# RingBottom.net
KiCad netlist of a schematic drawn in EAGLE
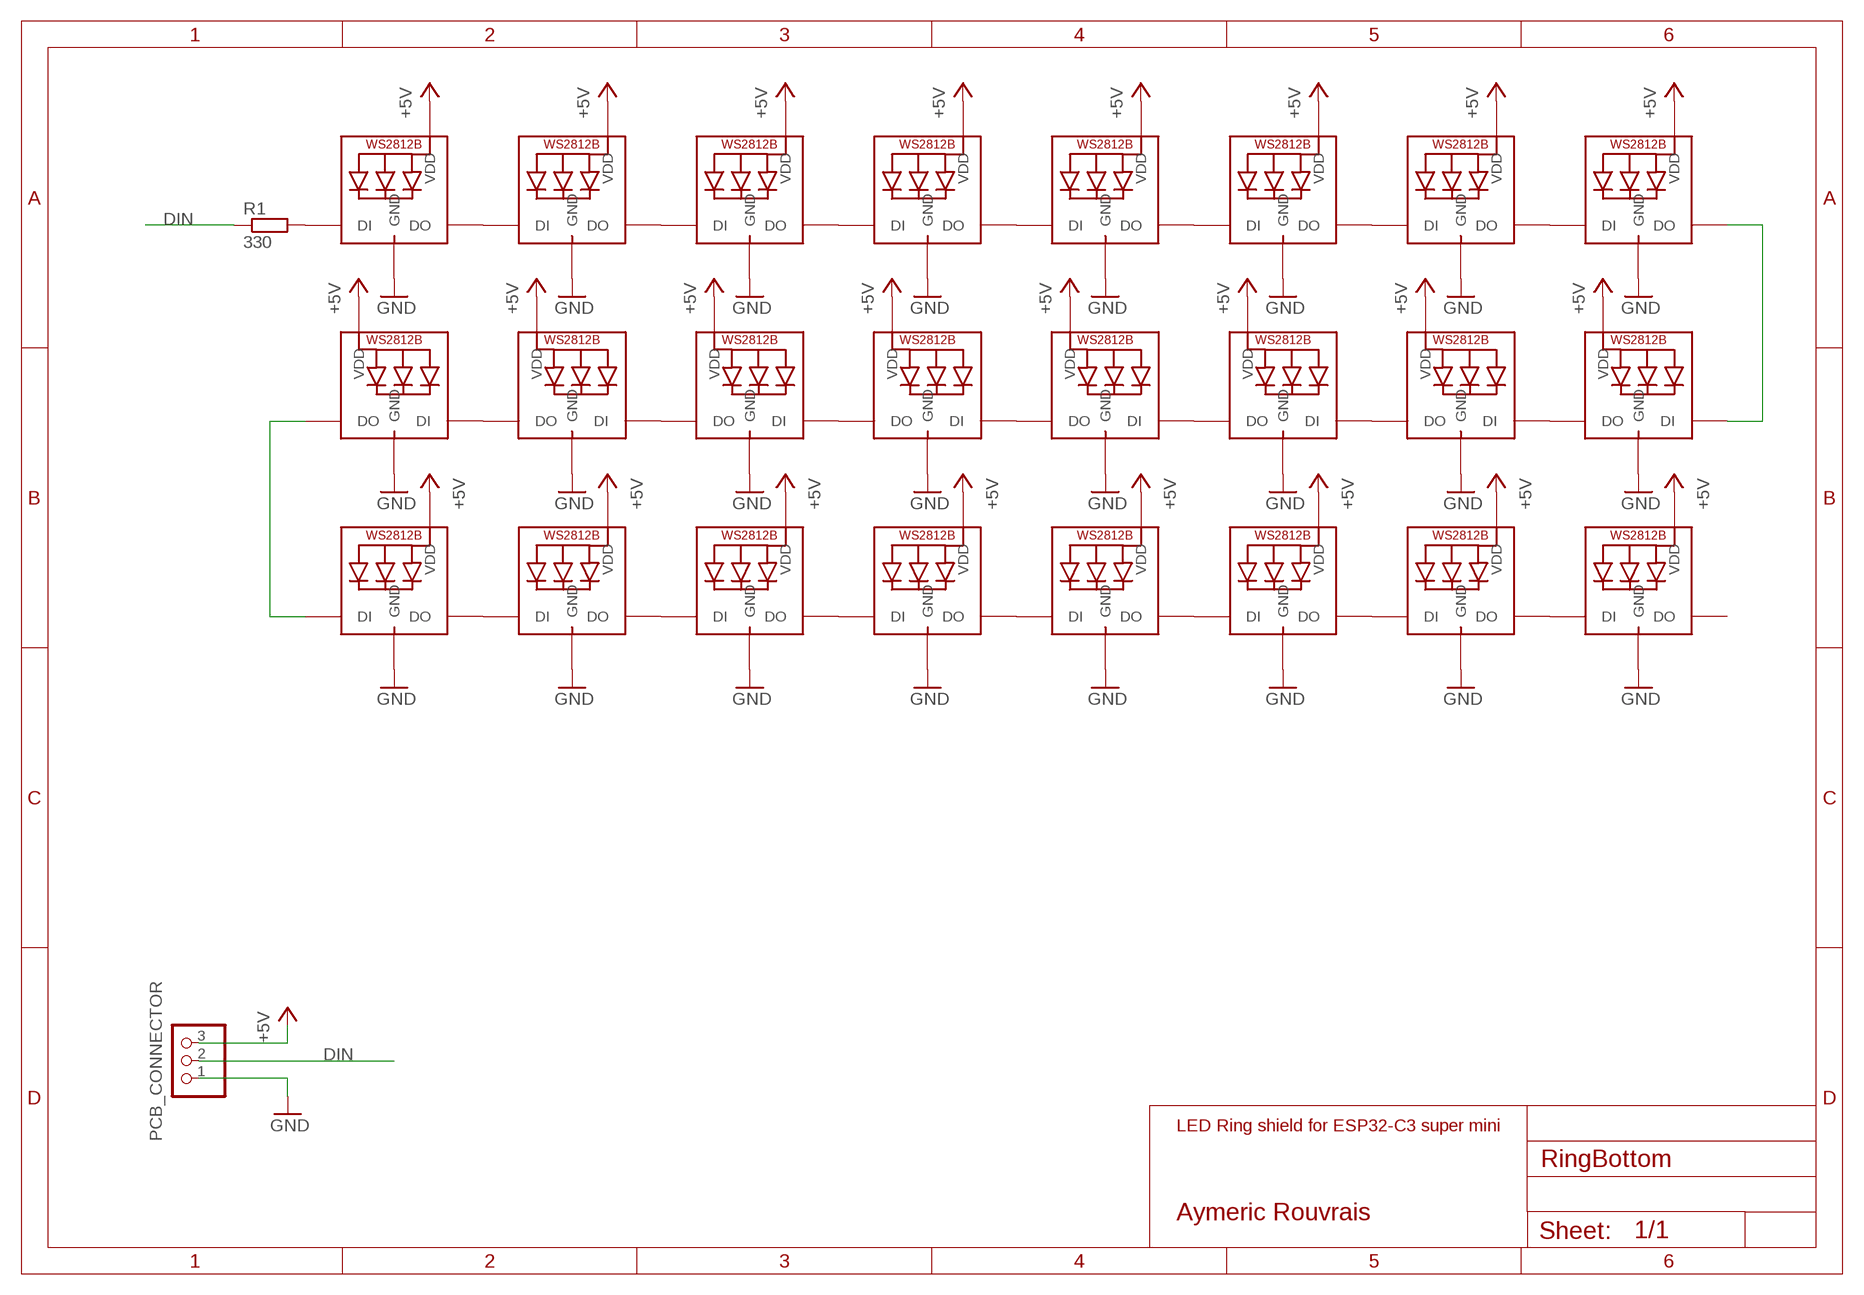
[diagram p0: schematic, sheet 1]

(export (version "E")
  (design (tool "Eeschema 10.0.6"))
  (components
    (comp (ref "LED1")
      (value "WS2812B5050")
      (footprint "eagle-import:WS2812B")
      (fields (field (name "MF") "Worldsemi") (field (name "MP") "WS2812B"))
      (libsource (lib "eagle-import") (part "WS2812B5050"))
    )
    (comp (ref "LED2")
      (value "WS2812B5050")
      (footprint "eagle-import:WS2812B")
      (fields (field (name "MF") "Worldsemi") (field (name "MP") "WS2812B"))
      (libsource (lib "eagle-import") (part "WS2812B5050"))
    )
    (comp (ref "LED3")
      (value "WS2812B5050")
      (footprint "eagle-import:WS2812B")
      (fields (field (name "MF") "Worldsemi") (field (name "MP") "WS2812B"))
      (libsource (lib "eagle-import") (part "WS2812B5050"))
    )
    (comp (ref "LED4")
      (value "WS2812B5050")
      (footprint "eagle-import:WS2812B")
      (fields (field (name "MF") "Worldsemi") (field (name "MP") "WS2812B"))
      (libsource (lib "eagle-import") (part "WS2812B5050"))
    )
    (comp (ref "LED5")
      (value "WS2812B5050")
      (footprint "eagle-import:WS2812B")
      (fields (field (name "MF") "Worldsemi") (field (name "MP") "WS2812B"))
      (libsource (lib "eagle-import") (part "WS2812B5050"))
    )
    (comp (ref "LED6")
      (value "WS2812B5050")
      (footprint "eagle-import:WS2812B")
      (fields (field (name "MF") "Worldsemi") (field (name "MP") "WS2812B"))
      (libsource (lib "eagle-import") (part "WS2812B5050"))
    )
    (comp (ref "LED7")
      (value "WS2812B5050")
      (footprint "eagle-import:WS2812B")
      (fields (field (name "MF") "Worldsemi") (field (name "MP") "WS2812B"))
      (libsource (lib "eagle-import") (part "WS2812B5050"))
    )
    (comp (ref "LED8")
      (value "WS2812B5050")
      (footprint "eagle-import:WS2812B")
      (fields (field (name "MF") "Worldsemi") (field (name "MP") "WS2812B"))
      (libsource (lib "eagle-import") (part "WS2812B5050"))
    )
    (comp (ref "LED9")
      (value "WS2812B5050")
      (footprint "eagle-import:WS2812B")
      (fields (field (name "MF") "Worldsemi") (field (name "MP") "WS2812B"))
      (libsource (lib "eagle-import") (part "WS2812B5050"))
    )
    (comp (ref "LED10")
      (value "WS2812B5050")
      (footprint "eagle-import:WS2812B")
      (fields (field (name "MF") "Worldsemi") (field (name "MP") "WS2812B"))
      (libsource (lib "eagle-import") (part "WS2812B5050"))
    )
    (comp (ref "LED11")
      (value "WS2812B5050")
      (footprint "eagle-import:WS2812B")
      (fields (field (name "MF") "Worldsemi") (field (name "MP") "WS2812B"))
      (libsource (lib "eagle-import") (part "WS2812B5050"))
    )
    (comp (ref "LED12")
      (value "WS2812B5050")
      (footprint "eagle-import:WS2812B")
      (fields (field (name "MF") "Worldsemi") (field (name "MP") "WS2812B"))
      (libsource (lib "eagle-import") (part "WS2812B5050"))
    )
    (comp (ref "LED13")
      (value "WS2812B5050")
      (footprint "eagle-import:WS2812B")
      (fields (field (name "MF") "Worldsemi") (field (name "MP") "WS2812B"))
      (libsource (lib "eagle-import") (part "WS2812B5050"))
    )
    (comp (ref "LED14")
      (value "WS2812B5050")
      (footprint "eagle-import:WS2812B")
      (fields (field (name "MF") "Worldsemi") (field (name "MP") "WS2812B"))
      (libsource (lib "eagle-import") (part "WS2812B5050"))
    )
    (comp (ref "LED15")
      (value "WS2812B5050")
      (footprint "eagle-import:WS2812B")
      (fields (field (name "MF") "Worldsemi") (field (name "MP") "WS2812B"))
      (libsource (lib "eagle-import") (part "WS2812B5050"))
    )
    (comp (ref "LED16")
      (value "WS2812B5050")
      (footprint "eagle-import:WS2812B")
      (fields (field (name "MF") "Worldsemi") (field (name "MP") "WS2812B"))
      (libsource (lib "eagle-import") (part "WS2812B5050"))
    )
    (comp (ref "LED17")
      (value "WS2812B5050")
      (footprint "eagle-import:WS2812B")
      (fields (field (name "MF") "Worldsemi") (field (name "MP") "WS2812B"))
      (libsource (lib "eagle-import") (part "WS2812B5050"))
    )
    (comp (ref "LED18")
      (value "WS2812B5050")
      (footprint "eagle-import:WS2812B")
      (fields (field (name "MF") "Worldsemi") (field (name "MP") "WS2812B"))
      (libsource (lib "eagle-import") (part "WS2812B5050"))
    )
    (comp (ref "LED19")
      (value "WS2812B5050")
      (footprint "eagle-import:WS2812B")
      (fields (field (name "MF") "Worldsemi") (field (name "MP") "WS2812B"))
      (libsource (lib "eagle-import") (part "WS2812B5050"))
    )
    (comp (ref "LED20")
      (value "WS2812B5050")
      (footprint "eagle-import:WS2812B")
      (fields (field (name "MF") "Worldsemi") (field (name "MP") "WS2812B"))
      (libsource (lib "eagle-import") (part "WS2812B5050"))
    )
    (comp (ref "LED21")
      (value "WS2812B5050")
      (footprint "eagle-import:WS2812B")
      (fields (field (name "MF") "Worldsemi") (field (name "MP") "WS2812B"))
      (libsource (lib "eagle-import") (part "WS2812B5050"))
    )
    (comp (ref "LED22")
      (value "WS2812B5050")
      (footprint "eagle-import:WS2812B")
      (fields (field (name "MF") "Worldsemi") (field (name "MP") "WS2812B"))
      (libsource (lib "eagle-import") (part "WS2812B5050"))
    )
    (comp (ref "LED23")
      (value "WS2812B5050")
      (footprint "eagle-import:WS2812B")
      (fields (field (name "MF") "Worldsemi") (field (name "MP") "WS2812B"))
      (libsource (lib "eagle-import") (part "WS2812B5050"))
    )
    (comp (ref "LED24")
      (value "WS2812B5050")
      (footprint "eagle-import:WS2812B")
      (fields (field (name "MF") "Worldsemi") (field (name "MP") "WS2812B"))
      (libsource (lib "eagle-import") (part "WS2812B5050"))
    )
    (comp (ref "PCB_CONNECTOR")
      (value "PINHD-1X3")
      (footprint "eagle-import:1X03")
      (libsource (lib "eagle-import") (part "PINHD-1X3"))
    )
    (comp (ref "R1")
      (value "330")
      (footprint "eagle-import:0204_7")
      (libsource (lib "eagle-import") (part "R-EU_0204/7"))
    )
  )
  (nets
    (net (code "1") (name "+5V") (class "Default")
      (node (ref "LED1") (pin "1-VDD") (pinfunction "VDD_1-VDD") (pintype "power_in"))
      (node (ref "LED10") (pin "1-VDD") (pinfunction "VDD_1-VDD") (pintype "power_in"))
      (node (ref "LED11") (pin "1-VDD") (pinfunction "VDD_1-VDD") (pintype "power_in"))
      (node (ref "LED12") (pin "1-VDD") (pinfunction "VDD_1-VDD") (pintype "power_in"))
      (node (ref "LED13") (pin "1-VDD") (pinfunction "VDD_1-VDD") (pintype "power_in"))
      (node (ref "LED14") (pin "1-VDD") (pinfunction "VDD_1-VDD") (pintype "power_in"))
      (node (ref "LED15") (pin "1-VDD") (pinfunction "VDD_1-VDD") (pintype "power_in"))
      (node (ref "LED16") (pin "1-VDD") (pinfunction "VDD_1-VDD") (pintype "power_in"))
      (node (ref "LED17") (pin "1-VDD") (pinfunction "VDD_1-VDD") (pintype "power_in"))
      (node (ref "LED18") (pin "1-VDD") (pinfunction "VDD_1-VDD") (pintype "power_in"))
      (node (ref "LED19") (pin "1-VDD") (pinfunction "VDD_1-VDD") (pintype "power_in"))
      (node (ref "LED2") (pin "1-VDD") (pinfunction "VDD_1-VDD") (pintype "power_in"))
      (node (ref "LED20") (pin "1-VDD") (pinfunction "VDD_1-VDD") (pintype "power_in"))
      (node (ref "LED21") (pin "1-VDD") (pinfunction "VDD_1-VDD") (pintype "power_in"))
      (node (ref "LED22") (pin "1-VDD") (pinfunction "VDD_1-VDD") (pintype "power_in"))
      (node (ref "LED23") (pin "1-VDD") (pinfunction "VDD_1-VDD") (pintype "power_in"))
      (node (ref "LED24") (pin "1-VDD") (pinfunction "VDD_1-VDD") (pintype "power_in"))
      (node (ref "LED3") (pin "1-VDD") (pinfunction "VDD_1-VDD") (pintype "power_in"))
      (node (ref "LED4") (pin "1-VDD") (pinfunction "VDD_1-VDD") (pintype "power_in"))
      (node (ref "LED5") (pin "1-VDD") (pinfunction "VDD_1-VDD") (pintype "power_in"))
      (node (ref "LED6") (pin "1-VDD") (pinfunction "VDD_1-VDD") (pintype "power_in"))
      (node (ref "LED7") (pin "1-VDD") (pinfunction "VDD_1-VDD") (pintype "power_in"))
      (node (ref "LED8") (pin "1-VDD") (pinfunction "VDD_1-VDD") (pintype "power_in"))
      (node (ref "LED9") (pin "1-VDD") (pinfunction "VDD_1-VDD") (pintype "power_in"))
      (node (ref "PCB_CONNECTOR") (pin "3") (pinfunction "3_3") (pintype "passive"))
    )
    (net (code "2") (name "/DIN") (class "Default")
      (node (ref "PCB_CONNECTOR") (pin "2") (pinfunction "2_2") (pintype "passive"))
      (node (ref "R1") (pin "1") (pinfunction "1_1") (pintype "passive"))
    )
    (net (code "3") (name "GND") (class "Default")
      (node (ref "LED1") (pin "3-GND") (pinfunction "GND_3-GND") (pintype "power_in"))
      (node (ref "LED10") (pin "3-GND") (pinfunction "GND_3-GND") (pintype "power_in"))
      (node (ref "LED11") (pin "3-GND") (pinfunction "GND_3-GND") (pintype "power_in"))
      (node (ref "LED12") (pin "3-GND") (pinfunction "GND_3-GND") (pintype "power_in"))
      (node (ref "LED13") (pin "3-GND") (pinfunction "GND_3-GND") (pintype "power_in"))
      (node (ref "LED14") (pin "3-GND") (pinfunction "GND_3-GND") (pintype "power_in"))
      (node (ref "LED15") (pin "3-GND") (pinfunction "GND_3-GND") (pintype "power_in"))
      (node (ref "LED16") (pin "3-GND") (pinfunction "GND_3-GND") (pintype "power_in"))
      (node (ref "LED17") (pin "3-GND") (pinfunction "GND_3-GND") (pintype "power_in"))
      (node (ref "LED18") (pin "3-GND") (pinfunction "GND_3-GND") (pintype "power_in"))
      (node (ref "LED19") (pin "3-GND") (pinfunction "GND_3-GND") (pintype "power_in"))
      (node (ref "LED2") (pin "3-GND") (pinfunction "GND_3-GND") (pintype "power_in"))
      (node (ref "LED20") (pin "3-GND") (pinfunction "GND_3-GND") (pintype "power_in"))
      (node (ref "LED21") (pin "3-GND") (pinfunction "GND_3-GND") (pintype "power_in"))
      (node (ref "LED22") (pin "3-GND") (pinfunction "GND_3-GND") (pintype "power_in"))
      (node (ref "LED23") (pin "3-GND") (pinfunction "GND_3-GND") (pintype "power_in"))
      (node (ref "LED24") (pin "3-GND") (pinfunction "GND_3-GND") (pintype "power_in"))
      (node (ref "LED3") (pin "3-GND") (pinfunction "GND_3-GND") (pintype "power_in"))
      (node (ref "LED4") (pin "3-GND") (pinfunction "GND_3-GND") (pintype "power_in"))
      (node (ref "LED5") (pin "3-GND") (pinfunction "GND_3-GND") (pintype "power_in"))
      (node (ref "LED6") (pin "3-GND") (pinfunction "GND_3-GND") (pintype "power_in"))
      (node (ref "LED7") (pin "3-GND") (pinfunction "GND_3-GND") (pintype "power_in"))
      (node (ref "LED8") (pin "3-GND") (pinfunction "GND_3-GND") (pintype "power_in"))
      (node (ref "LED9") (pin "3-GND") (pinfunction "GND_3-GND") (pintype "power_in"))
      (node (ref "PCB_CONNECTOR") (pin "1") (pinfunction "1_1") (pintype "passive"))
    )
    (net (code "4") (name "Net-(LED1-DI)") (class "Default")
      (node (ref "LED1") (pin "4-DIN") (pinfunction "DI_4-DIN") (pintype "input"))
      (node (ref "R1") (pin "2") (pinfunction "2_2") (pintype "passive"))
    )
    (net (code "5") (name "Net-(LED1-DO)") (class "Default")
      (node (ref "LED1") (pin "2-DOUT") (pinfunction "DO_2-DOUT") (pintype "output"))
      (node (ref "LED2") (pin "4-DIN") (pinfunction "DI_4-DIN") (pintype "input"))
    )
    (net (code "6") (name "Net-(LED2-DO)") (class "Default")
      (node (ref "LED2") (pin "2-DOUT") (pinfunction "DO_2-DOUT") (pintype "output"))
      (node (ref "LED3") (pin "4-DIN") (pinfunction "DI_4-DIN") (pintype "input"))
    )
    (net (code "7") (name "Net-(LED3-DO)") (class "Default")
      (node (ref "LED3") (pin "2-DOUT") (pinfunction "DO_2-DOUT") (pintype "output"))
      (node (ref "LED4") (pin "4-DIN") (pinfunction "DI_4-DIN") (pintype "input"))
    )
    (net (code "8") (name "Net-(LED4-DO)") (class "Default")
      (node (ref "LED4") (pin "2-DOUT") (pinfunction "DO_2-DOUT") (pintype "output"))
      (node (ref "LED5") (pin "4-DIN") (pinfunction "DI_4-DIN") (pintype "input"))
    )
    (net (code "9") (name "Net-(LED5-DO)") (class "Default")
      (node (ref "LED5") (pin "2-DOUT") (pinfunction "DO_2-DOUT") (pintype "output"))
      (node (ref "LED6") (pin "4-DIN") (pinfunction "DI_4-DIN") (pintype "input"))
    )
    (net (code "10") (name "Net-(LED6-DO)") (class "Default")
      (node (ref "LED6") (pin "2-DOUT") (pinfunction "DO_2-DOUT") (pintype "output"))
      (node (ref "LED7") (pin "4-DIN") (pinfunction "DI_4-DIN") (pintype "input"))
    )
    (net (code "11") (name "Net-(LED7-DO)") (class "Default")
      (node (ref "LED7") (pin "2-DOUT") (pinfunction "DO_2-DOUT") (pintype "output"))
      (node (ref "LED8") (pin "4-DIN") (pinfunction "DI_4-DIN") (pintype "input"))
    )
    (net (code "12") (name "Net-(LED8-DO)") (class "Default")
      (node (ref "LED8") (pin "2-DOUT") (pinfunction "DO_2-DOUT") (pintype "output"))
      (node (ref "LED9") (pin "4-DIN") (pinfunction "DI_4-DIN") (pintype "input"))
    )
    (net (code "13") (name "Net-(LED10-DI)") (class "Default")
      (node (ref "LED10") (pin "4-DIN") (pinfunction "DI_4-DIN") (pintype "input"))
      (node (ref "LED9") (pin "2-DOUT") (pinfunction "DO_2-DOUT") (pintype "output"))
    )
    (net (code "14") (name "Net-(LED10-DO)") (class "Default")
      (node (ref "LED10") (pin "2-DOUT") (pinfunction "DO_2-DOUT") (pintype "output"))
      (node (ref "LED11") (pin "4-DIN") (pinfunction "DI_4-DIN") (pintype "input"))
    )
    (net (code "15") (name "Net-(LED11-DO)") (class "Default")
      (node (ref "LED11") (pin "2-DOUT") (pinfunction "DO_2-DOUT") (pintype "output"))
      (node (ref "LED12") (pin "4-DIN") (pinfunction "DI_4-DIN") (pintype "input"))
    )
    (net (code "16") (name "Net-(LED12-DO)") (class "Default")
      (node (ref "LED12") (pin "2-DOUT") (pinfunction "DO_2-DOUT") (pintype "output"))
      (node (ref "LED13") (pin "4-DIN") (pinfunction "DI_4-DIN") (pintype "input"))
    )
    (net (code "17") (name "Net-(LED13-DO)") (class "Default")
      (node (ref "LED13") (pin "2-DOUT") (pinfunction "DO_2-DOUT") (pintype "output"))
      (node (ref "LED14") (pin "4-DIN") (pinfunction "DI_4-DIN") (pintype "input"))
    )
    (net (code "18") (name "Net-(LED14-DO)") (class "Default")
      (node (ref "LED14") (pin "2-DOUT") (pinfunction "DO_2-DOUT") (pintype "output"))
      (node (ref "LED15") (pin "4-DIN") (pinfunction "DI_4-DIN") (pintype "input"))
    )
    (net (code "19") (name "Net-(LED15-DO)") (class "Default")
      (node (ref "LED15") (pin "2-DOUT") (pinfunction "DO_2-DOUT") (pintype "output"))
      (node (ref "LED16") (pin "4-DIN") (pinfunction "DI_4-DIN") (pintype "input"))
    )
    (net (code "20") (name "Net-(LED16-DO)") (class "Default")
      (node (ref "LED16") (pin "2-DOUT") (pinfunction "DO_2-DOUT") (pintype "output"))
      (node (ref "LED17") (pin "4-DIN") (pinfunction "DI_4-DIN") (pintype "input"))
    )
    (net (code "21") (name "Net-(LED17-DO)") (class "Default")
      (node (ref "LED17") (pin "2-DOUT") (pinfunction "DO_2-DOUT") (pintype "output"))
      (node (ref "LED18") (pin "4-DIN") (pinfunction "DI_4-DIN") (pintype "input"))
    )
    (net (code "22") (name "Net-(LED18-DO)") (class "Default")
      (node (ref "LED18") (pin "2-DOUT") (pinfunction "DO_2-DOUT") (pintype "output"))
      (node (ref "LED19") (pin "4-DIN") (pinfunction "DI_4-DIN") (pintype "input"))
    )
    (net (code "23") (name "Net-(LED19-DO)") (class "Default")
      (node (ref "LED19") (pin "2-DOUT") (pinfunction "DO_2-DOUT") (pintype "output"))
      (node (ref "LED20") (pin "4-DIN") (pinfunction "DI_4-DIN") (pintype "input"))
    )
    (net (code "24") (name "Net-(LED20-DO)") (class "Default")
      (node (ref "LED20") (pin "2-DOUT") (pinfunction "DO_2-DOUT") (pintype "output"))
      (node (ref "LED21") (pin "4-DIN") (pinfunction "DI_4-DIN") (pintype "input"))
    )
    (net (code "25") (name "Net-(LED21-DO)") (class "Default")
      (node (ref "LED21") (pin "2-DOUT") (pinfunction "DO_2-DOUT") (pintype "output"))
      (node (ref "LED22") (pin "4-DIN") (pinfunction "DI_4-DIN") (pintype "input"))
    )
    (net (code "26") (name "Net-(LED22-DO)") (class "Default")
      (node (ref "LED22") (pin "2-DOUT") (pinfunction "DO_2-DOUT") (pintype "output"))
      (node (ref "LED23") (pin "4-DIN") (pinfunction "DI_4-DIN") (pintype "input"))
    )
    (net (code "27") (name "Net-(LED23-DO)") (class "Default")
      (node (ref "LED23") (pin "2-DOUT") (pinfunction "DO_2-DOUT") (pintype "output"))
      (node (ref "LED24") (pin "4-DIN") (pinfunction "DI_4-DIN") (pintype "input"))
    )
    (net (code "28") (name "unconnected-(LED24-DO-Pad2-DOUT)") (class "Default")
      (node (ref "LED24") (pin "2-DOUT") (pinfunction "DO_2-DOUT") (pintype "output"))
    )
  )
)
